# hab_tracker.net
KiCad netlist of a schematic drawn in EAGLE
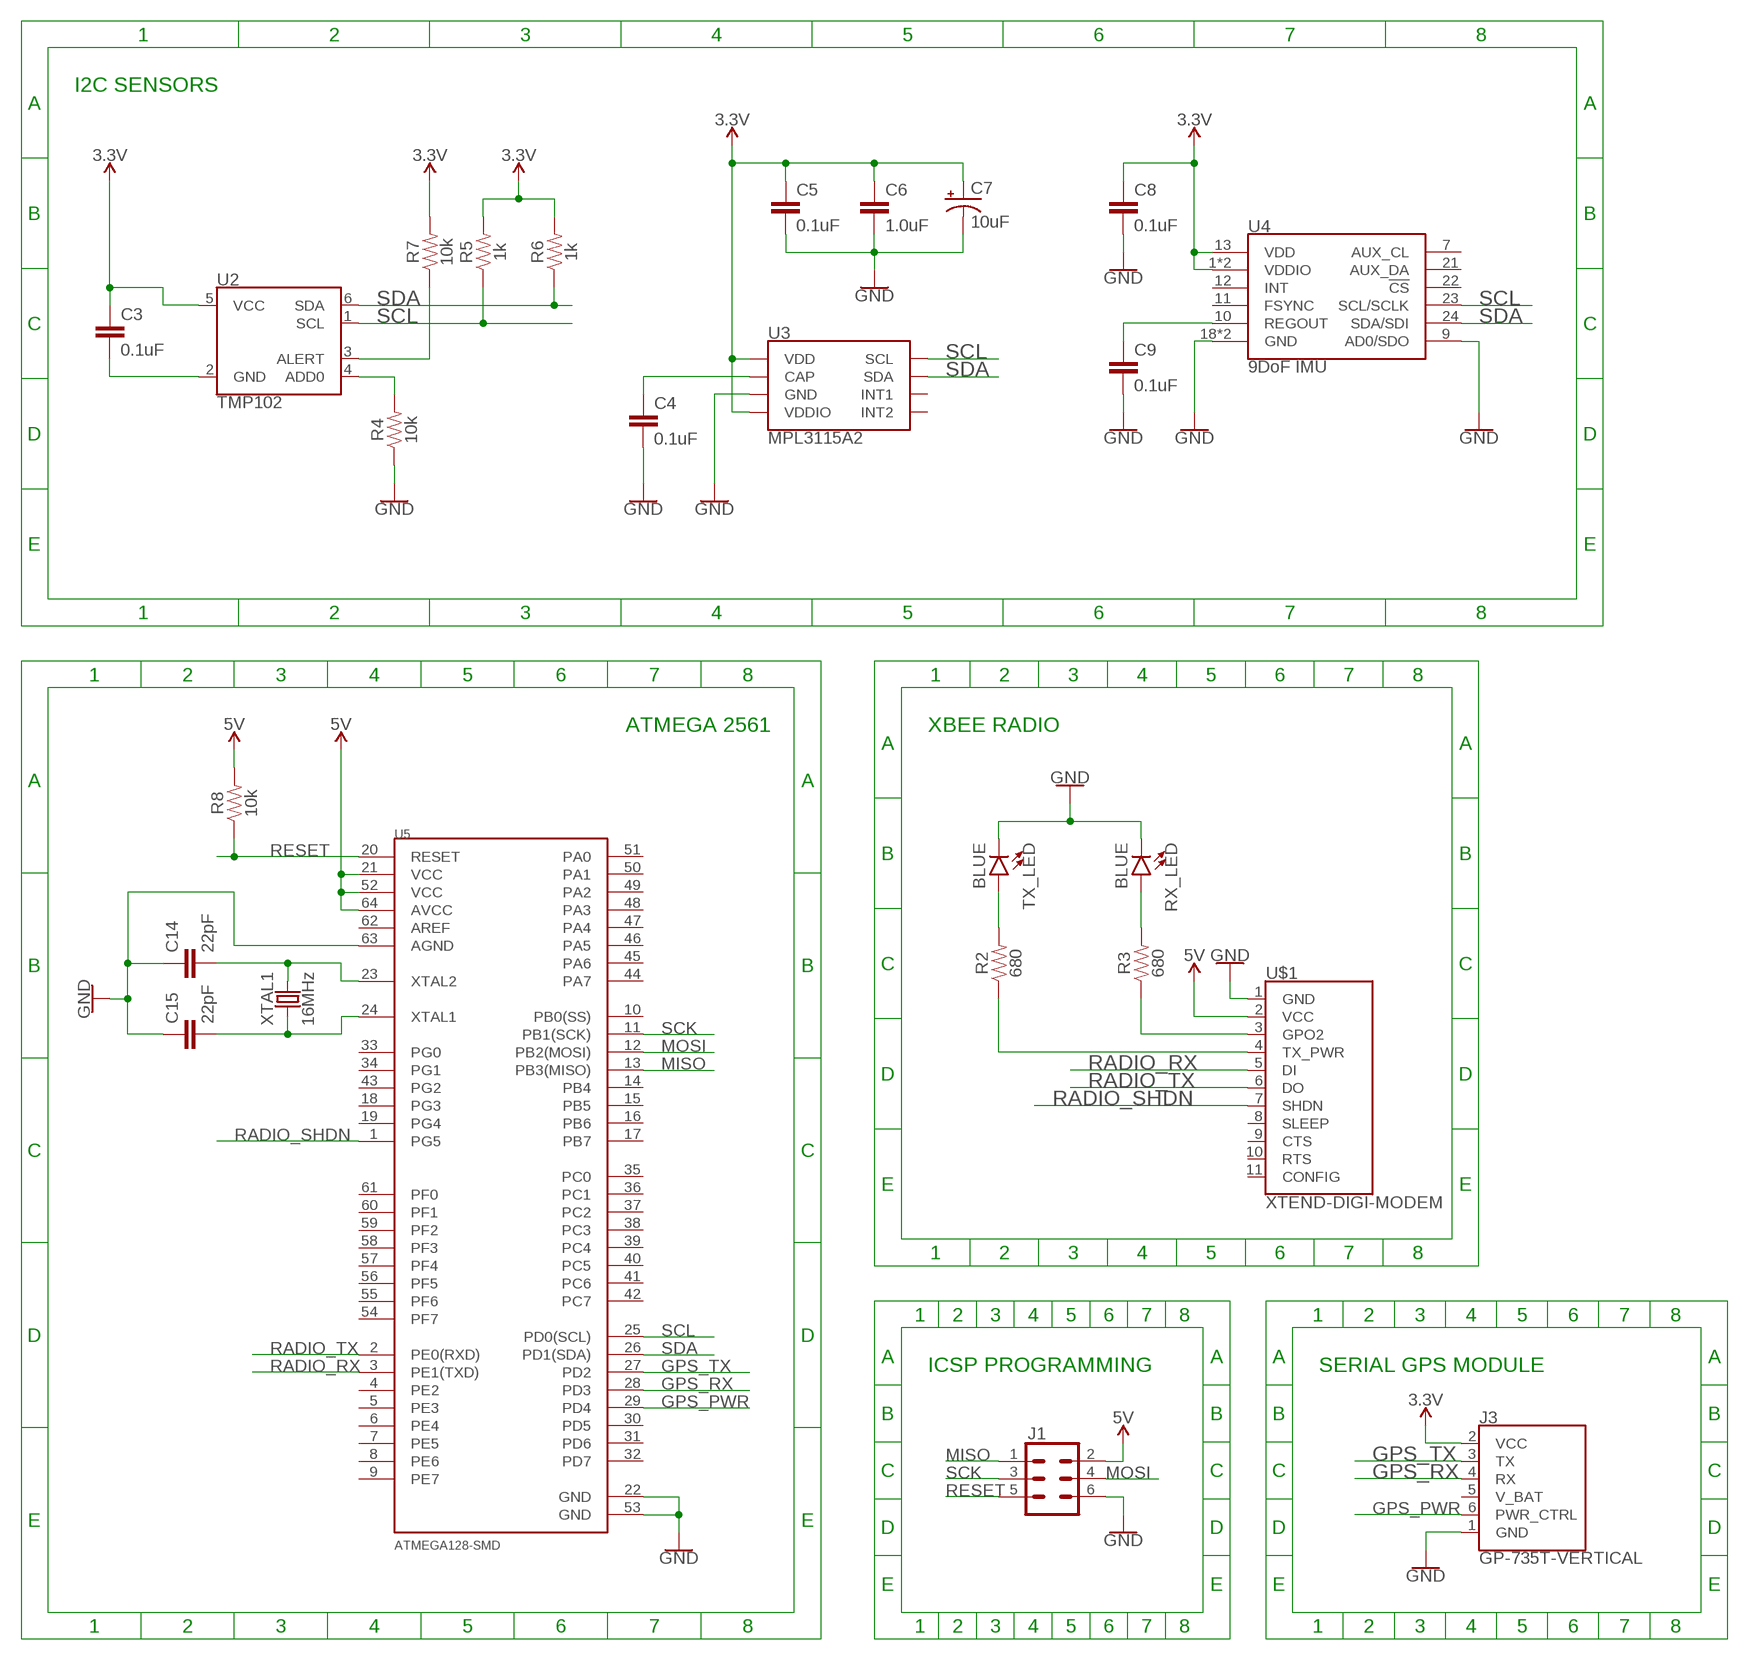
[diagram p0: schematic, sheet 1]
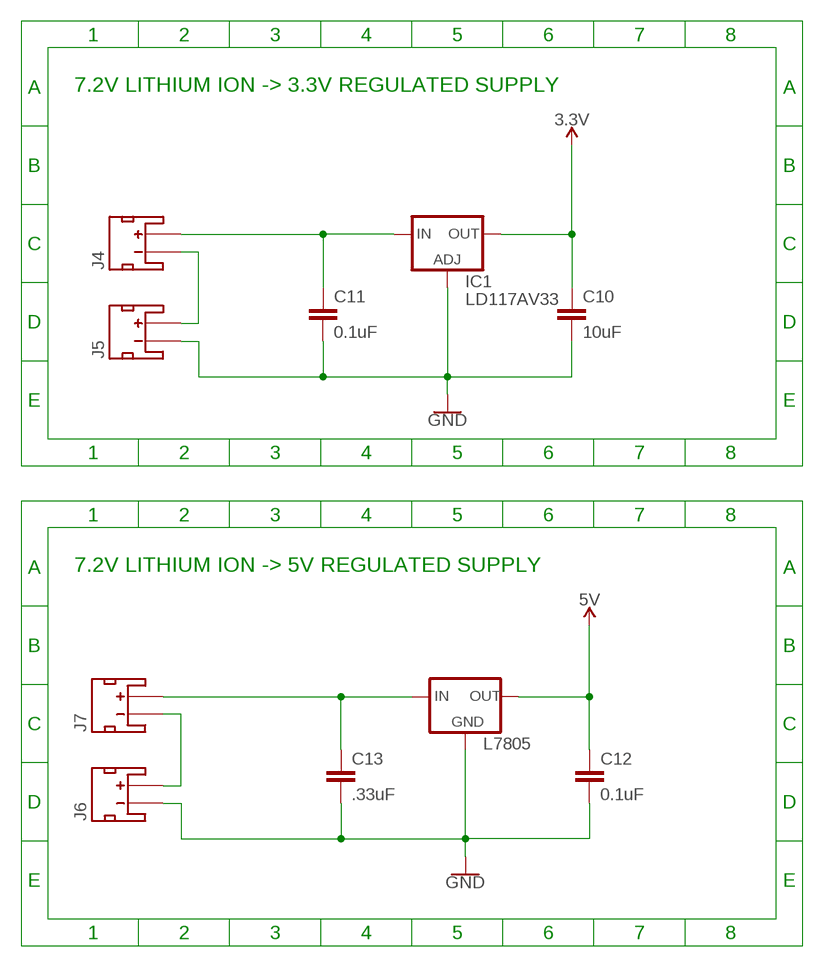
[diagram p1: schematic, sheet 2]

(export (version "E")
  (design (tool "Eeschema 10.0.6"))
  (components
    (comp (ref "C3")
      (value "0.1uF")
      (footprint "eagle-import:0603")
      (libsource (lib "eagle-import") (part "0.1UF-0603-25V-(+80/-20%)"))
    )
    (comp (ref "C4")
      (value "0.1uF")
      (footprint "eagle-import:0603")
      (libsource (lib "eagle-import") (part "0.1UF-0603-25V-(+80/-20%)"))
    )
    (comp (ref "C5")
      (value "0.1uF")
      (footprint "eagle-import:CAP-PTH-SMALL-KIT")
      (libsource (lib "eagle-import") (part "0.1UF-KIT-EZ-50V-20%"))
    )
    (comp (ref "C6")
      (value "1.0uF")
      (footprint "eagle-import:0603")
      (libsource (lib "eagle-import") (part "1.0UF-0603-16V-10%"))
    )
    (comp (ref "C7")
      (value "10uF")
      (footprint "eagle-import:0603-POLAR")
      (libsource (lib "eagle-import") (part "10UF-POLAR-0603-6.3V-20%(TANT)"))
    )
    (comp (ref "C8")
      (value "0.1uF")
      (footprint "eagle-import:CAP-PTH-SMALL-KIT")
      (libsource (lib "eagle-import") (part "0.1UF-KIT-EZ-50V-20%"))
    )
    (comp (ref "C9")
      (value "0.1uF")
      (footprint "eagle-import:CAP-PTH-SMALL-KIT")
      (libsource (lib "eagle-import") (part "0.1UF-KIT-EZ-50V-20%"))
    )
    (comp (ref "C14")
      (value "22pF")
      (footprint "eagle-import:0603")
      (libsource (lib "eagle-import") (part "22PF-0603-50V-5%"))
    )
    (comp (ref "C15")
      (value "22pF")
      (footprint "eagle-import:0603")
      (libsource (lib "eagle-import") (part "22PF-0603-50V-5%"))
    )
    (comp (ref "J1")
      (value "CONN_03X2SHROUD")
      (footprint "eagle-import:2X3-SHROUDED")
      (libsource (lib "eagle-import") (part "CONN_03X2SHROUD"))
    )
    (comp (ref "J3")
      (value "GP-735T-VERTICAL")
      (footprint "eagle-import:JST-6PIN-1MM")
      (libsource (lib "eagle-import") (part "GP-735T-VERTICAL"))
    )
    (comp (ref "R2")
      (value "680")
      (footprint "eagle-import:0603")
      (libsource (lib "eagle-import") (part "680OHM-0603-1/10W-5%"))
    )
    (comp (ref "R3")
      (value "680")
      (footprint "eagle-import:0603")
      (libsource (lib "eagle-import") (part "680OHM-0603-1/10W-5%"))
    )
    (comp (ref "R4")
      (value "10k")
      (footprint "eagle-import:0603")
      (libsource (lib "eagle-import") (part "10KOHM-0603-1/10W-1%"))
    )
    (comp (ref "R5")
      (value "1k")
      (footprint "eagle-import:0603")
      (libsource (lib "eagle-import") (part "1KOHM-0603-1/10W-1%"))
    )
    (comp (ref "R6")
      (value "1k")
      (footprint "eagle-import:0603")
      (libsource (lib "eagle-import") (part "1KOHM-0603-1/10W-1%"))
    )
    (comp (ref "R7")
      (value "10k")
      (footprint "eagle-import:0603")
      (libsource (lib "eagle-import") (part "10KOHM-0603-1/10W-1%"))
    )
    (comp (ref "R8")
      (value "10k")
      (footprint "eagle-import:0603")
      (libsource (lib "eagle-import") (part "10KOHM-0603-1/10W-1%"))
    )
    (comp (ref "RX_LED")
      (value "BLUE")
      (footprint "eagle-import:LED-1206")
      (libsource (lib "eagle-import") (part "LED-BLUE1206"))
    )
    (comp (ref "TX_LED")
      (value "BLUE")
      (footprint "eagle-import:LED-1206")
      (libsource (lib "eagle-import") (part "LED-BLUE1206"))
    )
    (comp (ref "U$1")
      (value "XTEND-DIGI-MODEM")
      (footprint "eagle-import:XTEND-DIGI-MODEM")
      (libsource (lib "eagle-import") (part "XTEND-DIGI-MODEM"))
    )
    (comp (ref "U2")
      (value "TMP102")
      (footprint "eagle-import:SOT563")
      (libsource (lib "eagle-import") (part "TMP102"))
    )
    (comp (ref "U3")
      (value "MPL3115A2")
      (footprint "eagle-import:LGA-8-5X3")
      (libsource (lib "eagle-import") (part "MPL3115A2"))
    )
    (comp (ref "U4")
      (value "9DoF IMU")
      (footprint "eagle-import:QFN24-3X3")
      (libsource (lib "eagle-import") (part "MPU-9250"))
    )
    (comp (ref "U5")
      (value "ATMEGA128-SMD")
      (footprint "eagle-import:TQFP64_14X14MM")
      (libsource (lib "eagle-import") (part "ATMEGA128-SMD"))
    )
    (comp (ref "XTAL1")
      (value "16MHz")
      (footprint "eagle-import:CRYSTAL-SMD-5X3.2-4PAD")
      (libsource (lib "eagle-import") (part "CRYSTAL-16MHZSMD-5X3.2"))
    )
    (comp (ref "C10")
      (value "10uF")
      (footprint "eagle-import:0603")
      (libsource (lib "eagle-import") (part "10UF-0603-6.3V-20%"))
    )
    (comp (ref "C11")
      (value "0.1uF")
      (footprint "eagle-import:0603")
      (libsource (lib "eagle-import") (part "0.1UF-0603-25V-(+80/-20%)"))
    )
    (comp (ref "C12")
      (value "0.1uF")
      (footprint "eagle-import:0603")
      (libsource (lib "eagle-import") (part "0.1UF-0603-25V-(+80/-20%)"))
    )
    (comp (ref "C13")
      (value ".33uF")
      (footprint "eagle-import:0603")
      (libsource (lib "eagle-import") (part "1.0NF/1000PF-0603-50V-10%"))
    )
    (comp (ref "IC1")
      (value "LD117AV33")
      (footprint "eagle-import:TO220L1")
      (libsource (lib "eagle-import") (part "LD117A?V33"))
    )
    (comp (ref "J4")
      (value "JST_2MM_MALE")
      (footprint "eagle-import:JST-2-SMD")
      (libsource (lib "eagle-import") (part "JST_2MM_MALE"))
    )
    (comp (ref "J5")
      (value "JST_2MM_MALE")
      (footprint "eagle-import:JST-2-SMD")
      (libsource (lib "eagle-import") (part "JST_2MM_MALE"))
    )
    (comp (ref "J6")
      (value "JST_2MM_MALE")
      (footprint "eagle-import:JST-2-SMD")
      (libsource (lib "eagle-import") (part "JST_2MM_MALE"))
    )
    (comp (ref "J7")
      (value "JST_2MM_MALE")
      (footprint "eagle-import:JST-2-SMD")
      (libsource (lib "eagle-import") (part "JST_2MM_MALE"))
    )
    (comp (ref "L7805")
      (value "V_REG_78XX-TO-220")
      (footprint "eagle-import:TO-220-ALT")
      (libsource (lib "eagle-import") (part "V_REG_78XX-TO-220"))
    )
  )
  (nets
    (net (code "1") (name "3.3V") (class "Default")
      (node (ref "C10") (pin "1") (pinfunction "1_1") (pintype "passive"))
      (node (ref "C3") (pin "1") (pinfunction "1_1") (pintype "passive"))
      (node (ref "C5") (pin "1") (pinfunction "1_1") (pintype "passive"))
      (node (ref "C6") (pin "1") (pinfunction "1_1") (pintype "passive"))
      (node (ref "C7") (pin "+") (pinfunction "+_+") (pintype "passive"))
      (node (ref "C8") (pin "1") (pinfunction "1_1") (pintype "passive"))
      (node (ref "IC1") (pin "2") (pinfunction "OUT_2") (pintype "passive"))
      (node (ref "J3") (pin "2") (pinfunction "VCC_2") (pintype "bidirectional"))
      (node (ref "R5") (pin "2") (pinfunction "2_2") (pintype "passive"))
      (node (ref "R6") (pin "2") (pinfunction "2_2") (pintype "passive"))
      (node (ref "R7") (pin "2") (pinfunction "2_2") (pintype "passive"))
      (node (ref "U2") (pin "5") (pinfunction "VCC_5") (pintype "bidirectional"))
      (node (ref "U3") (pin "1") (pinfunction "VDD_1") (pintype "power_in"))
      (node (ref "U3") (pin "4") (pinfunction "VDDIO_4") (pintype "power_in"))
      (node (ref "U4") (pin "1") (pinfunction "VDDIO_1") (pintype "bidirectional"))
      (node (ref "U4") (pin "13") (pinfunction "VDD_13") (pintype "bidirectional"))
      (node (ref "U4") (pin "8") (pinfunction "VDDIO_8") (pintype "bidirectional"))
    )
    (net (code "2") (name "5V") (class "Default")
      (node (ref "C12") (pin "1") (pinfunction "1_1") (pintype "passive"))
      (node (ref "J1") (pin "2") (pinfunction "2_2") (pintype "bidirectional"))
      (node (ref "L7805") (pin "OUT") (pinfunction "OUT_OUT") (pintype "passive"))
      (node (ref "R8") (pin "2") (pinfunction "2_2") (pintype "passive"))
      (node (ref "U$1") (pin "2") (pinfunction "VCC_2") (pintype "bidirectional"))
      (node (ref "U5") (pin "21") (pinfunction "VCC_21") (pintype "bidirectional"))
      (node (ref "U5") (pin "52") (pinfunction "VCC_52") (pintype "bidirectional"))
      (node (ref "U5") (pin "64") (pinfunction "AVCC_64") (pintype "bidirectional"))
    )
    (net (code "3") (name "GND") (class "Default")
      (node (ref "C10") (pin "2") (pinfunction "2_2") (pintype "passive"))
      (node (ref "C11") (pin "2") (pinfunction "2_2") (pintype "passive"))
      (node (ref "C12") (pin "2") (pinfunction "2_2") (pintype "passive"))
      (node (ref "C13") (pin "2") (pinfunction "2_2") (pintype "passive"))
      (node (ref "C14") (pin "1") (pinfunction "1_1") (pintype "passive"))
      (node (ref "C15") (pin "1") (pinfunction "1_1") (pintype "passive"))
      (node (ref "C4") (pin "2") (pinfunction "2_2") (pintype "passive"))
      (node (ref "C5") (pin "2") (pinfunction "2_2") (pintype "passive"))
      (node (ref "C6") (pin "2") (pinfunction "2_2") (pintype "passive"))
      (node (ref "C7") (pin "-") (pinfunction "-_-") (pintype "passive"))
      (node (ref "C8") (pin "2") (pinfunction "2_2") (pintype "passive"))
      (node (ref "C9") (pin "2") (pinfunction "2_2") (pintype "passive"))
      (node (ref "IC1") (pin "1") (pinfunction "ADJ_1") (pintype "input"))
      (node (ref "J1") (pin "6") (pinfunction "6_6") (pintype "bidirectional"))
      (node (ref "J3") (pin "1") (pinfunction "GND_1") (pintype "bidirectional"))
      (node (ref "J5") (pin "1") (pinfunction "-_1") (pintype "bidirectional"))
      (node (ref "J6") (pin "1") (pinfunction "-_1") (pintype "bidirectional"))
      (node (ref "L7805") (pin "GND") (pinfunction "GND_GND") (pintype "input"))
      (node (ref "R4") (pin "1") (pinfunction "1_1") (pintype "passive"))
      (node (ref "RX_LED") (pin "C") (pinfunction "C_C") (pintype "passive"))
      (node (ref "TX_LED") (pin "C") (pinfunction "C_C") (pintype "passive"))
      (node (ref "U$1") (pin "1") (pinfunction "GND_1") (pintype "bidirectional"))
      (node (ref "U3") (pin "3") (pinfunction "GND_3") (pintype "power_in"))
      (node (ref "U4") (pin "18") (pinfunction "GND_18") (pintype "bidirectional"))
      (node (ref "U4") (pin "20") (pinfunction "GND_20") (pintype "bidirectional"))
      (node (ref "U4") (pin "9") (pinfunction "AD0/SDO_9") (pintype "bidirectional"))
      (node (ref "U5") (pin "22") (pinfunction "GND_22") (pintype "bidirectional"))
      (node (ref "U5") (pin "53") (pinfunction "GND_53") (pintype "bidirectional"))
      (node (ref "U5") (pin "63") (pinfunction "AGND_63") (pintype "bidirectional"))
    )
    (net (code "4") (name "GPS_PWR") (class "Default")
      (node (ref "J3") (pin "6") (pinfunction "PWR_CTRL_6") (pintype "bidirectional"))
      (node (ref "U5") (pin "29") (pinfunction "PD4_29") (pintype "bidirectional"))
    )
    (net (code "5") (name "GPS_RX") (class "Default")
      (node (ref "J3") (pin "4") (pinfunction "RX_4") (pintype "bidirectional"))
      (node (ref "U5") (pin "28") (pinfunction "PD3_28") (pintype "bidirectional"))
    )
    (net (code "6") (name "GPS_TX") (class "Default")
      (node (ref "J3") (pin "3") (pinfunction "TX_3") (pintype "bidirectional"))
      (node (ref "U5") (pin "27") (pinfunction "PD2_27") (pintype "bidirectional"))
    )
    (net (code "7") (name "MISO") (class "Default")
      (node (ref "J1") (pin "1") (pinfunction "1_1") (pintype "bidirectional"))
      (node (ref "U5") (pin "13") (pinfunction "PB3(MISO)_13") (pintype "bidirectional"))
    )
    (net (code "8") (name "MOSI") (class "Default")
      (node (ref "J1") (pin "4") (pinfunction "4_4") (pintype "bidirectional"))
      (node (ref "U5") (pin "12") (pinfunction "PB2(MOSI)_12") (pintype "bidirectional"))
    )
    (net (code "9") (name "Net-(IC1-IN)") (class "Default")
      (node (ref "C11") (pin "1") (pinfunction "1_1") (pintype "passive"))
      (node (ref "IC1") (pin "3") (pinfunction "IN_3") (pintype "input"))
      (node (ref "J4") (pin "2") (pinfunction "+_2") (pintype "bidirectional"))
    )
    (net (code "10") (name "Net-(J4--)") (class "Default")
      (node (ref "J4") (pin "1") (pinfunction "-_1") (pintype "bidirectional"))
      (node (ref "J5") (pin "2") (pinfunction "+_2") (pintype "bidirectional"))
    )
    (net (code "11") (name "Net-(J6-+)") (class "Default")
      (node (ref "J6") (pin "2") (pinfunction "+_2") (pintype "bidirectional"))
      (node (ref "J7") (pin "1") (pinfunction "-_1") (pintype "bidirectional"))
    )
    (net (code "12") (name "Net-(J7-+)") (class "Default")
      (node (ref "C13") (pin "1") (pinfunction "1_1") (pintype "passive"))
      (node (ref "J7") (pin "2") (pinfunction "+_2") (pintype "bidirectional"))
      (node (ref "L7805") (pin "IN") (pinfunction "IN_IN") (pintype "input"))
    )
    (net (code "13") (name "Net-(R2-Pad2)") (class "Default")
      (node (ref "R2") (pin "2") (pinfunction "2_2") (pintype "passive"))
      (node (ref "TX_LED") (pin "A") (pinfunction "A_A") (pintype "passive"))
    )
    (net (code "14") (name "Net-(R3-Pad2)") (class "Default")
      (node (ref "R3") (pin "2") (pinfunction "2_2") (pintype "passive"))
      (node (ref "RX_LED") (pin "A") (pinfunction "A_A") (pintype "passive"))
    )
    (net (code "15") (name "Net-(U$1-GPO2)") (class "Default")
      (node (ref "R3") (pin "1") (pinfunction "1_1") (pintype "passive"))
      (node (ref "U$1") (pin "3") (pinfunction "GPO2_3") (pintype "bidirectional"))
    )
    (net (code "16") (name "Net-(U$1-TX_PWR)") (class "Default")
      (node (ref "R2") (pin "1") (pinfunction "1_1") (pintype "passive"))
      (node (ref "U$1") (pin "4") (pinfunction "TX_PWR_4") (pintype "bidirectional"))
    )
    (net (code "17") (name "Net-(U2-ADD0)") (class "Default")
      (node (ref "R4") (pin "2") (pinfunction "2_2") (pintype "passive"))
      (node (ref "U2") (pin "4") (pinfunction "ADD0_4") (pintype "bidirectional"))
    )
    (net (code "18") (name "Net-(U2-ALERT)") (class "Default")
      (node (ref "R7") (pin "1") (pinfunction "1_1") (pintype "passive"))
      (node (ref "U2") (pin "3") (pinfunction "ALERT_3") (pintype "bidirectional"))
    )
    (net (code "19") (name "Net-(U2-GND)") (class "Default")
      (node (ref "C3") (pin "2") (pinfunction "2_2") (pintype "passive"))
      (node (ref "U2") (pin "2") (pinfunction "GND_2") (pintype "bidirectional"))
    )
    (net (code "20") (name "Net-(U3-CAP)") (class "Default")
      (node (ref "C4") (pin "1") (pinfunction "1_1") (pintype "passive"))
      (node (ref "U3") (pin "2") (pinfunction "CAP_2") (pintype "power_in"))
    )
    (net (code "21") (name "Net-(U4-REGOUT)") (class "Default")
      (node (ref "C9") (pin "1") (pinfunction "1_1") (pintype "passive"))
      (node (ref "U4") (pin "10") (pinfunction "REGOUT_10") (pintype "bidirectional"))
    )
    (net (code "22") (name "Net-(U5-XTAL1)") (class "Default")
      (node (ref "C15") (pin "2") (pinfunction "2_2") (pintype "passive"))
      (node (ref "U5") (pin "24") (pinfunction "XTAL1_24") (pintype "bidirectional"))
      (node (ref "XTAL1") (pin "1") (pinfunction "1_1") (pintype "passive"))
    )
    (net (code "23") (name "Net-(U5-XTAL2)") (class "Default")
      (node (ref "C14") (pin "2") (pinfunction "2_2") (pintype "passive"))
      (node (ref "U5") (pin "23") (pinfunction "XTAL2_23") (pintype "bidirectional"))
      (node (ref "XTAL1") (pin "3") (pinfunction "2_3") (pintype "passive"))
    )
    (net (code "24") (name "RADIO_RX") (class "Default")
      (node (ref "U$1") (pin "5") (pinfunction "DI_5") (pintype "bidirectional"))
      (node (ref "U5") (pin "3") (pinfunction "PE1(TXD)_3") (pintype "bidirectional"))
    )
    (net (code "25") (name "RADIO_SHDN") (class "Default")
      (node (ref "U$1") (pin "7") (pinfunction "SHDN_7") (pintype "bidirectional"))
      (node (ref "U5") (pin "1") (pinfunction "PG5_1") (pintype "bidirectional"))
    )
    (net (code "26") (name "RADIO_TX") (class "Default")
      (node (ref "U$1") (pin "6") (pinfunction "DO_6") (pintype "bidirectional"))
      (node (ref "U5") (pin "2") (pinfunction "PE0(RXD)_2") (pintype "bidirectional"))
    )
    (net (code "27") (name "RESET") (class "Default")
      (node (ref "J1") (pin "5") (pinfunction "5_5") (pintype "bidirectional"))
      (node (ref "R8") (pin "1") (pinfunction "1_1") (pintype "passive"))
      (node (ref "U5") (pin "20") (pinfunction "RESET_20") (pintype "bidirectional"))
    )
    (net (code "28") (name "SCK") (class "Default")
      (node (ref "J1") (pin "3") (pinfunction "3_3") (pintype "bidirectional"))
      (node (ref "U5") (pin "11") (pinfunction "PB1(SCK)_11") (pintype "bidirectional"))
    )
    (net (code "29") (name "SCL") (class "Default")
      (node (ref "R5") (pin "1") (pinfunction "1_1") (pintype "passive"))
      (node (ref "U2") (pin "1") (pinfunction "SCL_1") (pintype "bidirectional"))
      (node (ref "U3") (pin "8") (pinfunction "SCL_8") (pintype "bidirectional"))
      (node (ref "U4") (pin "23") (pinfunction "SCL/SCLK_23") (pintype "bidirectional"))
      (node (ref "U5") (pin "25") (pinfunction "PD0(SCL)_25") (pintype "bidirectional"))
    )
    (net (code "30") (name "SDA") (class "Default")
      (node (ref "R6") (pin "1") (pinfunction "1_1") (pintype "passive"))
      (node (ref "U2") (pin "6") (pinfunction "SDA_6") (pintype "bidirectional"))
      (node (ref "U3") (pin "7") (pinfunction "SDA_7") (pintype "bidirectional"))
      (node (ref "U4") (pin "24") (pinfunction "SDA/SDI_24") (pintype "bidirectional"))
      (node (ref "U5") (pin "26") (pinfunction "PD1(SDA)_26") (pintype "bidirectional"))
    )
    (net (code "31") (name "unconnected-(J3-V_BAT-Pad5)") (class "Default")
      (node (ref "J3") (pin "5") (pinfunction "V_BAT_5") (pintype "bidirectional"))
    )
    (net (code "32") (name "unconnected-(J4-PAD1-PadNC1)") (class "Default")
      (node (ref "J4") (pin "NC1") (pinfunction "PAD1_NC1") (pintype "bidirectional"))
    )
    (net (code "33") (name "unconnected-(J4-PAD2-PadNC2)") (class "Default")
      (node (ref "J4") (pin "NC2") (pinfunction "PAD2_NC2") (pintype "bidirectional"))
    )
    (net (code "34") (name "unconnected-(J5-PAD1-PadNC1)") (class "Default")
      (node (ref "J5") (pin "NC1") (pinfunction "PAD1_NC1") (pintype "bidirectional"))
    )
    (net (code "35") (name "unconnected-(J5-PAD2-PadNC2)") (class "Default")
      (node (ref "J5") (pin "NC2") (pinfunction "PAD2_NC2") (pintype "bidirectional"))
    )
    (net (code "36") (name "unconnected-(J6-PAD1-PadNC1)") (class "Default")
      (node (ref "J6") (pin "NC1") (pinfunction "PAD1_NC1") (pintype "bidirectional"))
    )
    (net (code "37") (name "unconnected-(J6-PAD2-PadNC2)") (class "Default")
      (node (ref "J6") (pin "NC2") (pinfunction "PAD2_NC2") (pintype "bidirectional"))
    )
    (net (code "38") (name "unconnected-(J7-PAD1-PadNC1)") (class "Default")
      (node (ref "J7") (pin "NC1") (pinfunction "PAD1_NC1") (pintype "bidirectional"))
    )
    (net (code "39") (name "unconnected-(J7-PAD2-PadNC2)") (class "Default")
      (node (ref "J7") (pin "NC2") (pinfunction "PAD2_NC2") (pintype "bidirectional"))
    )
    (net (code "40") (name "unconnected-(U$1-CONFIG-Pad11)") (class "Default")
      (node (ref "U$1") (pin "11") (pinfunction "CONFIG_11") (pintype "bidirectional"))
    )
    (net (code "41") (name "unconnected-(U$1-CTS-Pad9)") (class "Default")
      (node (ref "U$1") (pin "9") (pinfunction "CTS_9") (pintype "bidirectional"))
    )
    (net (code "42") (name "unconnected-(U$1-RTS-Pad10)") (class "Default")
      (node (ref "U$1") (pin "10") (pinfunction "RTS_10") (pintype "bidirectional"))
    )
    (net (code "43") (name "unconnected-(U$1-SLEEP-Pad8)") (class "Default")
      (node (ref "U$1") (pin "8") (pinfunction "SLEEP_8") (pintype "bidirectional"))
    )
    (net (code "44") (name "unconnected-(U3-INT1-Pad6)") (class "Default")
      (node (ref "U3") (pin "6") (pinfunction "INT1_6") (pintype "output"))
    )
    (net (code "45") (name "unconnected-(U3-INT2-Pad5)") (class "Default")
      (node (ref "U3") (pin "5") (pinfunction "INT2_5") (pintype "output"))
    )
    (net (code "46") (name "unconnected-(U4-AUX_CL-Pad7)") (class "Default")
      (node (ref "U4") (pin "7") (pinfunction "AUX_CL_7") (pintype "bidirectional"))
    )
    (net (code "47") (name "unconnected-(U4-AUX_DA-Pad21)") (class "Default")
      (node (ref "U4") (pin "21") (pinfunction "AUX_DA_21") (pintype "bidirectional"))
    )
    (net (code "48") (name "unconnected-(U4-FSYNC-Pad11)") (class "Default")
      (node (ref "U4") (pin "11") (pinfunction "FSYNC_11") (pintype "bidirectional"))
    )
    (net (code "49") (name "unconnected-(U4-INT-Pad12)") (class "Default")
      (node (ref "U4") (pin "12") (pinfunction "INT_12") (pintype "bidirectional"))
    )
    (net (code "50") (name "unconnected-(U4-~{CS}-Pad22)") (class "Default")
      (node (ref "U4") (pin "22") (pinfunction "~{CS}_22") (pintype "bidirectional"))
    )
    (net (code "51") (name "unconnected-(U5-AREF-Pad62)") (class "Default")
      (node (ref "U5") (pin "62") (pinfunction "AREF_62") (pintype "bidirectional"))
    )
    (net (code "52") (name "unconnected-(U5-PA0-Pad51)") (class "Default")
      (node (ref "U5") (pin "51") (pinfunction "PA0_51") (pintype "bidirectional"))
    )
    (net (code "53") (name "unconnected-(U5-PA1-Pad50)") (class "Default")
      (node (ref "U5") (pin "50") (pinfunction "PA1_50") (pintype "bidirectional"))
    )
    (net (code "54") (name "unconnected-(U5-PA2-Pad49)") (class "Default")
      (node (ref "U5") (pin "49") (pinfunction "PA2_49") (pintype "bidirectional"))
    )
    (net (code "55") (name "unconnected-(U5-PA3-Pad48)") (class "Default")
      (node (ref "U5") (pin "48") (pinfunction "PA3_48") (pintype "bidirectional"))
    )
    (net (code "56") (name "unconnected-(U5-PA4-Pad47)") (class "Default")
      (node (ref "U5") (pin "47") (pinfunction "PA4_47") (pintype "bidirectional"))
    )
    (net (code "57") (name "unconnected-(U5-PA5-Pad46)") (class "Default")
      (node (ref "U5") (pin "46") (pinfunction "PA5_46") (pintype "bidirectional"))
    )
    (net (code "58") (name "unconnected-(U5-PA6-Pad45)") (class "Default")
      (node (ref "U5") (pin "45") (pinfunction "PA6_45") (pintype "bidirectional"))
    )
    (net (code "59") (name "unconnected-(U5-PA7-Pad44)") (class "Default")
      (node (ref "U5") (pin "44") (pinfunction "PA7_44") (pintype "bidirectional"))
    )
    (net (code "60") (name "unconnected-(U5-PB0(SS)-Pad10)") (class "Default")
      (node (ref "U5") (pin "10") (pinfunction "PB0(SS)_10") (pintype "bidirectional"))
    )
    (net (code "61") (name "unconnected-(U5-PB4-Pad14)") (class "Default")
      (node (ref "U5") (pin "14") (pinfunction "PB4_14") (pintype "bidirectional"))
    )
    (net (code "62") (name "unconnected-(U5-PB5-Pad15)") (class "Default")
      (node (ref "U5") (pin "15") (pinfunction "PB5_15") (pintype "bidirectional"))
    )
    (net (code "63") (name "unconnected-(U5-PB6-Pad16)") (class "Default")
      (node (ref "U5") (pin "16") (pinfunction "PB6_16") (pintype "bidirectional"))
    )
    (net (code "64") (name "unconnected-(U5-PB7-Pad17)") (class "Default")
      (node (ref "U5") (pin "17") (pinfunction "PB7_17") (pintype "bidirectional"))
    )
    (net (code "65") (name "unconnected-(U5-PC0-Pad35)") (class "Default")
      (node (ref "U5") (pin "35") (pinfunction "PC0_35") (pintype "bidirectional"))
    )
    (net (code "66") (name "unconnected-(U5-PC1-Pad36)") (class "Default")
      (node (ref "U5") (pin "36") (pinfunction "PC1_36") (pintype "bidirectional"))
    )
    (net (code "67") (name "unconnected-(U5-PC2-Pad37)") (class "Default")
      (node (ref "U5") (pin "37") (pinfunction "PC2_37") (pintype "bidirectional"))
    )
    (net (code "68") (name "unconnected-(U5-PC3-Pad38)") (class "Default")
      (node (ref "U5") (pin "38") (pinfunction "PC3_38") (pintype "bidirectional"))
    )
    (net (code "69") (name "unconnected-(U5-PC4-Pad39)") (class "Default")
      (node (ref "U5") (pin "39") (pinfunction "PC4_39") (pintype "bidirectional"))
    )
    (net (code "70") (name "unconnected-(U5-PC5-Pad40)") (class "Default")
      (node (ref "U5") (pin "40") (pinfunction "PC5_40") (pintype "bidirectional"))
    )
    (net (code "71") (name "unconnected-(U5-PC6-Pad41)") (class "Default")
      (node (ref "U5") (pin "41") (pinfunction "PC6_41") (pintype "bidirectional"))
    )
    (net (code "72") (name "unconnected-(U5-PC7-Pad42)") (class "Default")
      (node (ref "U5") (pin "42") (pinfunction "PC7_42") (pintype "bidirectional"))
    )
    (net (code "73") (name "unconnected-(U5-PD5-Pad30)") (class "Default")
      (node (ref "U5") (pin "30") (pinfunction "PD5_30") (pintype "bidirectional"))
    )
    (net (code "74") (name "unconnected-(U5-PD6-Pad31)") (class "Default")
      (node (ref "U5") (pin "31") (pinfunction "PD6_31") (pintype "bidirectional"))
    )
    (net (code "75") (name "unconnected-(U5-PD7-Pad32)") (class "Default")
      (node (ref "U5") (pin "32") (pinfunction "PD7_32") (pintype "bidirectional"))
    )
    (net (code "76") (name "unconnected-(U5-PE2-Pad4)") (class "Default")
      (node (ref "U5") (pin "4") (pinfunction "PE2_4") (pintype "bidirectional"))
    )
    (net (code "77") (name "unconnected-(U5-PE3-Pad5)") (class "Default")
      (node (ref "U5") (pin "5") (pinfunction "PE3_5") (pintype "bidirectional"))
    )
    (net (code "78") (name "unconnected-(U5-PE4-Pad6)") (class "Default")
      (node (ref "U5") (pin "6") (pinfunction "PE4_6") (pintype "bidirectional"))
    )
    (net (code "79") (name "unconnected-(U5-PE5-Pad7)") (class "Default")
      (node (ref "U5") (pin "7") (pinfunction "PE5_7") (pintype "bidirectional"))
    )
    (net (code "80") (name "unconnected-(U5-PE6-Pad8)") (class "Default")
      (node (ref "U5") (pin "8") (pinfunction "PE6_8") (pintype "bidirectional"))
    )
    (net (code "81") (name "unconnected-(U5-PE7-Pad9)") (class "Default")
      (node (ref "U5") (pin "9") (pinfunction "PE7_9") (pintype "bidirectional"))
    )
    (net (code "82") (name "unconnected-(U5-PF0-Pad61)") (class "Default")
      (node (ref "U5") (pin "61") (pinfunction "PF0_61") (pintype "bidirectional"))
    )
    (net (code "83") (name "unconnected-(U5-PF1-Pad60)") (class "Default")
      (node (ref "U5") (pin "60") (pinfunction "PF1_60") (pintype "bidirectional"))
    )
    (net (code "84") (name "unconnected-(U5-PF2-Pad59)") (class "Default")
      (node (ref "U5") (pin "59") (pinfunction "PF2_59") (pintype "bidirectional"))
    )
    (net (code "85") (name "unconnected-(U5-PF3-Pad58)") (class "Default")
      (node (ref "U5") (pin "58") (pinfunction "PF3_58") (pintype "bidirectional"))
    )
    (net (code "86") (name "unconnected-(U5-PF4-Pad57)") (class "Default")
      (node (ref "U5") (pin "57") (pinfunction "PF4_57") (pintype "bidirectional"))
    )
    (net (code "87") (name "unconnected-(U5-PF5-Pad56)") (class "Default")
      (node (ref "U5") (pin "56") (pinfunction "PF5_56") (pintype "bidirectional"))
    )
    (net (code "88") (name "unconnected-(U5-PF6-Pad55)") (class "Default")
      (node (ref "U5") (pin "55") (pinfunction "PF6_55") (pintype "bidirectional"))
    )
    (net (code "89") (name "unconnected-(U5-PF7-Pad54)") (class "Default")
      (node (ref "U5") (pin "54") (pinfunction "PF7_54") (pintype "bidirectional"))
    )
    (net (code "90") (name "unconnected-(U5-PG0-Pad33)") (class "Default")
      (node (ref "U5") (pin "33") (pinfunction "PG0_33") (pintype "bidirectional"))
    )
    (net (code "91") (name "unconnected-(U5-PG1-Pad34)") (class "Default")
      (node (ref "U5") (pin "34") (pinfunction "PG1_34") (pintype "bidirectional"))
    )
    (net (code "92") (name "unconnected-(U5-PG2-Pad43)") (class "Default")
      (node (ref "U5") (pin "43") (pinfunction "PG2_43") (pintype "bidirectional"))
    )
    (net (code "93") (name "unconnected-(U5-PG3-Pad18)") (class "Default")
      (node (ref "U5") (pin "18") (pinfunction "PG3_18") (pintype "bidirectional"))
    )
    (net (code "94") (name "unconnected-(U5-PG4-Pad19)") (class "Default")
      (node (ref "U5") (pin "19") (pinfunction "PG4_19") (pintype "bidirectional"))
    )
  )
)
